# sensors.net
KiCad netlist of a schematic drawn in Altium Designer
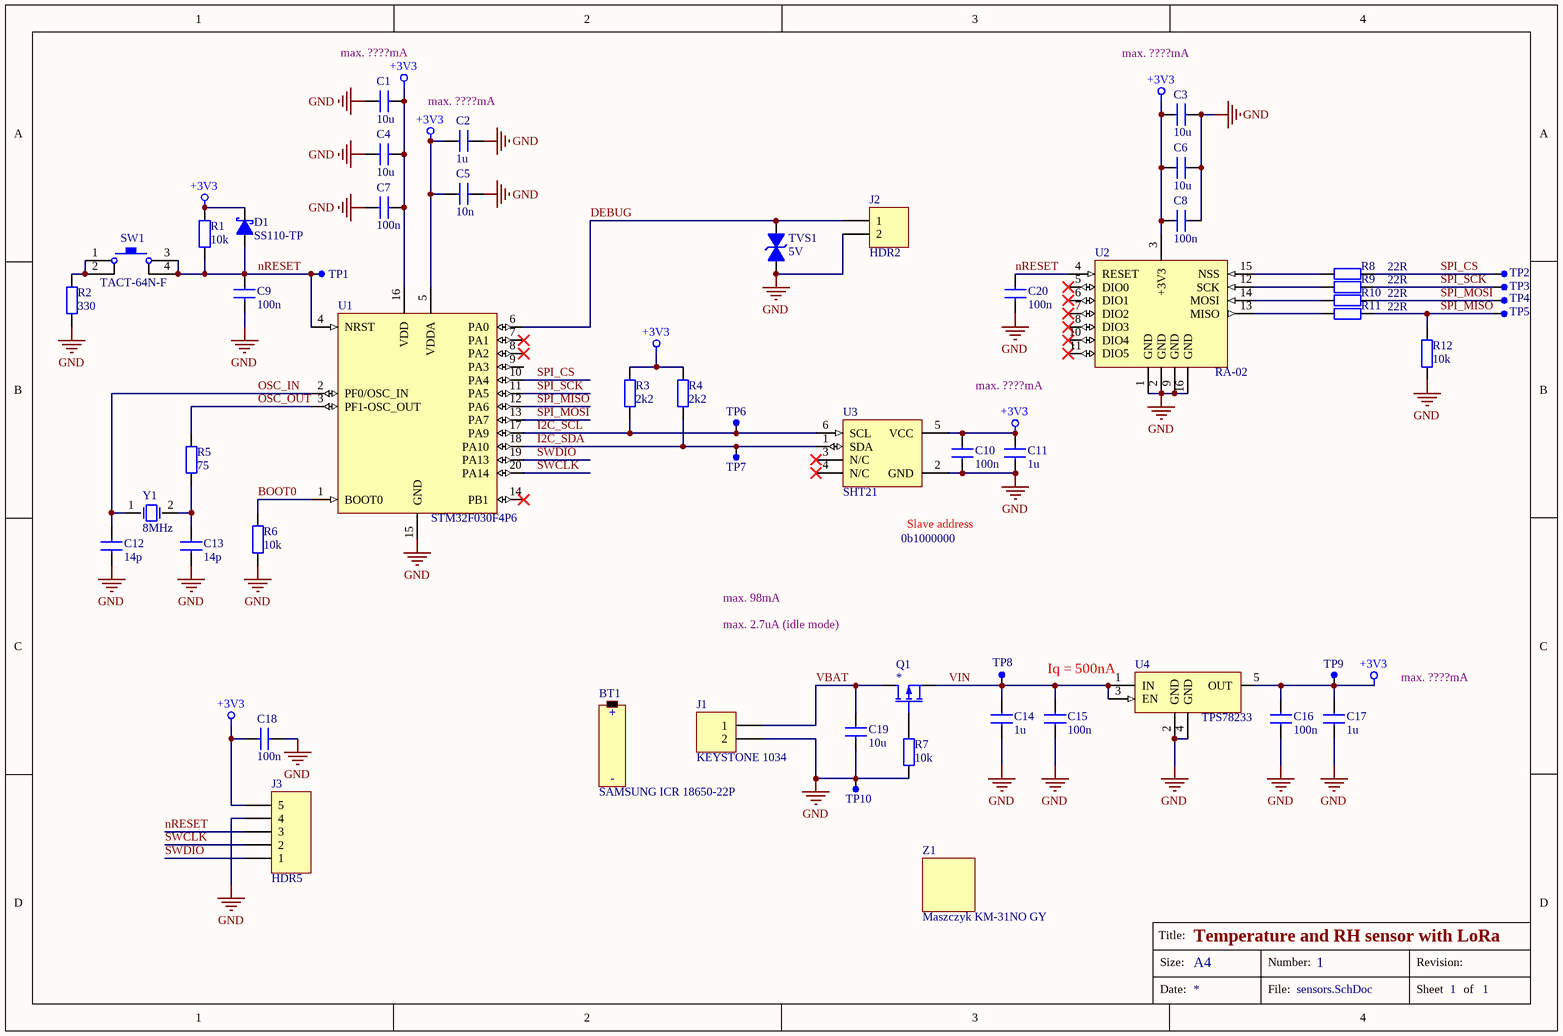
[diagram p0: sensors.SchDoc]

(export (version "E")
  (design (tool "Eeschema 10.0.6"))
  (components
    (comp (ref "BT1")
      (value "SAMSUNG ICR 18650-22P")
      (footprint "BATTERY_18650")
      (description "Multicell Battery")
      (fields (field (name "PUBLISHER") "Altium Limited"))
      (libsource (lib "mechanical") (part "Battery"))
    )
    (comp (ref "C1")
      (value "10u")
      (footprint "C_0805")
      (description "Capacitor")
      (libsource (lib "passive") (part "Capacitor"))
    )
    (comp (ref "C2")
      (value "1u")
      (footprint "C_0805")
      (description "Capacitor")
      (libsource (lib "passive") (part "Capacitor"))
    )
    (comp (ref "C3")
      (value "10u")
      (footprint "C_0805")
      (description "Capacitor")
      (libsource (lib "passive") (part "Capacitor"))
    )
    (comp (ref "C4")
      (value "10u")
      (footprint "C_0805")
      (description "Capacitor")
      (libsource (lib "passive") (part "Capacitor"))
    )
    (comp (ref "C5")
      (value "10n")
      (footprint "C_0805")
      (description "Capacitor")
      (libsource (lib "passive") (part "Capacitor"))
    )
    (comp (ref "C6")
      (value "10u")
      (footprint "C_0805")
      (description "Capacitor")
      (libsource (lib "passive") (part "Capacitor"))
    )
    (comp (ref "C7")
      (value "100n")
      (footprint "C_0805")
      (description "Capacitor")
      (libsource (lib "passive") (part "Capacitor"))
    )
    (comp (ref "C8")
      (value "100n")
      (footprint "C_0805")
      (description "Capacitor")
      (libsource (lib "passive") (part "Capacitor"))
    )
    (comp (ref "C9")
      (value "100n")
      (footprint "C_0805")
      (description "Capacitor")
      (libsource (lib "passive") (part "Capacitor"))
    )
    (comp (ref "C10")
      (value "100n")
      (footprint "C_0805")
      (description "Capacitor")
      (libsource (lib "boxer_pas") (part "Capacitor"))
    )
    (comp (ref "C11")
      (value "1u")
      (footprint "C_0805")
      (description "Capacitor")
      (libsource (lib "passive") (part "Capacitor"))
    )
    (comp (ref "C12")
      (value "14p")
      (footprint "C_0805")
      (description "Capacitor")
      (libsource (lib "passive") (part "Capacitor"))
    )
    (comp (ref "C13")
      (value "14p")
      (footprint "C_0805")
      (description "Capacitor")
      (libsource (lib "passive") (part "Capacitor"))
    )
    (comp (ref "C14")
      (value "1u")
      (footprint "C_0805")
      (description "Capacitor")
      (libsource (lib "passive") (part "Capacitor"))
    )
    (comp (ref "C15")
      (value "100n")
      (footprint "C_0805")
      (description "Capacitor")
      (libsource (lib "boxer_pas") (part "Capacitor"))
    )
    (comp (ref "C16")
      (value "100n")
      (footprint "C_0805")
      (description "Capacitor")
      (libsource (lib "boxer_pas") (part "Capacitor"))
    )
    (comp (ref "C17")
      (value "1u")
      (footprint "C_0805")
      (description "Capacitor")
      (libsource (lib "passive") (part "Capacitor"))
    )
    (comp (ref "C18")
      (value "100n")
      (footprint "C_0805")
      (description "Capacitor")
      (libsource (lib "passive") (part "Capacitor"))
    )
    (comp (ref "C19")
      (value "10u")
      (footprint "C_0805")
      (description "Capacitor")
      (libsource (lib "passive") (part "Capacitor"))
    )
    (comp (ref "C20")
      (value "100n")
      (footprint "C_0805")
      (description "Capacitor")
      (libsource (lib "boxer_pas") (part "Capacitor"))
    )
    (comp (ref "D1")
      (value "SS110-TP")
      (footprint "D_1206")
      (description "Schottky Diode")
      (libsource (lib "passive") (part "Diode Schottky"))
    )
    (comp (ref "J1")
      (value "KEYSTONE 1034")
      (footprint "KEYSTONE 1043")
      (description "Header, 2-Pin")
      (fields (field (name "Comment") "Header 2"))
      (libsource (lib "") (part "Header 2_1"))
    )
    (comp (ref "J2")
      (value "HDR2")
      (footprint "header 2.54mm 2pin")
      (description "Header, 2-Pin")
      (fields (field (name "Comment") "Header 2"))
      (libsource (lib "mechanical") (part "Header 2"))
    )
    (comp (ref "J3")
      (value "HDR5")
      (footprint "header 2.54mm 5pin")
      (description "Header, 5-Pin")
      (fields (field (name "Comment") "Header 5"))
      (libsource (lib "mechanical") (part "Header 5"))
    )
    (comp (ref "Q1")
      (value "MOSFET-P")
      (footprint "SOT-23")
      (description "P-Channel MOSFET")
      (fields (field (name "ALTIUM_VALUE") "*"))
      (libsource (lib "passive") (part "MOSFET-P"))
    )
    (comp (ref "R1")
      (value "10k")
      (footprint "R_0805")
      (description "Resistor")
      (libsource (lib "passive") (part "Resistor"))
    )
    (comp (ref "R2")
      (value "330")
      (footprint "R_0805")
      (description "Resistor")
      (libsource (lib "passive") (part "Resistor"))
    )
    (comp (ref "R3")
      (value "2k2")
      (footprint "R_0805")
      (description "Resistor")
      (libsource (lib "passive") (part "Resistor"))
    )
    (comp (ref "R4")
      (value "2k2")
      (footprint "R_0805")
      (description "Resistor")
      (libsource (lib "passive") (part "Resistor"))
    )
    (comp (ref "R5")
      (value "75")
      (footprint "R_0805")
      (description "Resistor")
      (libsource (lib "passive") (part "Resistor"))
    )
    (comp (ref "R6")
      (value "10k")
      (footprint "R_0805")
      (description "Resistor")
      (libsource (lib "passive") (part "Resistor"))
    )
    (comp (ref "R7")
      (value "10k")
      (footprint "R_0805")
      (description "Resistor")
      (libsource (lib "passive") (part "Resistor"))
    )
    (comp (ref "R8")
      (value "22R")
      (footprint "R_0805")
      (description "Resistor")
      (libsource (lib "") (part "Resistor_1"))
    )
    (comp (ref "R9")
      (value "22R")
      (footprint "R_0805")
      (description "Resistor")
      (libsource (lib "") (part "Resistor_1"))
    )
    (comp (ref "R10")
      (value "22R")
      (footprint "R_0805")
      (description "Resistor")
      (libsource (lib "") (part "Resistor_1"))
    )
    (comp (ref "R11")
      (value "22R")
      (footprint "R_0805")
      (description "Resistor")
      (libsource (lib "") (part "Resistor_1"))
    )
    (comp (ref "R12")
      (value "10k")
      (footprint "R_1206")
      (description "Resistor")
      (libsource (lib "passive") (part "Resistor"))
    )
    (comp (ref "SW1")
      (value "TACT-64N-F")
      (footprint "SPST_NO_1301")
      (description "Switch 4 Pins")
      (fields (field (name "Comment") "Switch-PB 4 Pins"))
      (libsource (lib "mechanical") (part "Switch-PB 4 Pins"))
    )
    (comp (ref "TP1")
      (value "TEST PAD")
      (footprint "PIN")
      (description "PAD 1.5mm")
      (libsource (lib "mechanical") (part "TEST_PAD"))
    )
    (comp (ref "TP2")
      (value "TEST PAD")
      (footprint "PIN")
      (description "PAD 1.5mm")
      (libsource (lib "mechanical") (part "TEST_PAD"))
    )
    (comp (ref "TP3")
      (value "TEST PAD")
      (footprint "PIN")
      (description "PAD 1.5mm")
      (libsource (lib "mechanical") (part "TEST_PAD"))
    )
    (comp (ref "TP4")
      (value "TEST PAD")
      (footprint "PIN")
      (description "PAD 1.5mm")
      (libsource (lib "mechanical") (part "TEST_PAD"))
    )
    (comp (ref "TP5")
      (value "TEST PAD")
      (footprint "PIN")
      (description "PAD 1.5mm")
      (libsource (lib "mechanical") (part "TEST_PAD"))
    )
    (comp (ref "TP6")
      (value "TEST PAD")
      (footprint "PIN")
      (description "PAD 1.5mm")
      (libsource (lib "mechanical") (part "TEST_PAD"))
    )
    (comp (ref "TP7")
      (value "TEST PAD")
      (footprint "PIN")
      (description "PAD 1.5mm")
      (libsource (lib "mechanical") (part "TEST_PAD"))
    )
    (comp (ref "TP8")
      (value "TEST PAD")
      (footprint "PIN")
      (description "PAD 1.5mm")
      (libsource (lib "mechanical") (part "TEST_PAD"))
    )
    (comp (ref "TP9")
      (value "TEST PAD")
      (footprint "PIN")
      (description "PAD 1.5mm")
      (libsource (lib "mechanical") (part "TEST_PAD"))
    )
    (comp (ref "TP10")
      (value "TEST PAD")
      (footprint "PIN")
      (description "PAD 1.5mm")
      (libsource (lib "mechanical") (part "TEST_PAD"))
    )
    (comp (ref "TVS1")
      (value "5V")
      (footprint "D_1206")
      (description "Transil")
      (fields (field (name "Comment") "SMAJ5.0ALFCT-ND"))
      (libsource (lib "passive") (part "Transil"))
    )
    (comp (ref "U1")
      (value "STM32F030F4P6")
      (footprint "TSSOP20")
      (description "Mikrokontroler ARM; Flash:16kB; 48MHz; SRAM:4kB; TSSOP20")
      (libsource (lib "digital") (part "STM32F030F4P6"))
    )
    (comp (ref "U2")
      (value "RA-02")
      (footprint "RA-02")
      (description "LoRa RA-02 SX1278 433MHz")
      (libsource (lib "digital") (part "RA-02 SX1278"))
    )
    (comp (ref "U3")
      (value "SHT21")
      (footprint "DFN6")
      (description "Humidity and Temperature Sensor IC")
      (libsource (lib "boxer_ic") (part "SHT21"))
    )
    (comp (ref "U4")
      (value "TPS78233")
      (footprint "SOP5(6)")
      (description "150-mA, ultra-low quiescent qurrent (500 nA) low-dropout linear regulator")
      (libsource (lib "digital") (part "TPS78233"))
    )
    (comp (ref "Y1")
      (value "8MHz")
      (footprint "CFPX_217")
      (description "Crystal Oscillator")
      (fields (field (name "Comment") "7A-8.000MAAE-T"))
      (libsource (lib "passive") (part "XTAL"))
    )
    (comp (ref "Z1")
      (value "Maszczyk KM-31NO GY")
      (footprint "KM-31NO GY")
      (description "X:80mm; Y:114mm; Z:32mm; wentylowana; ABS")
      (libsource (lib "mechanical") (part "KM-31NO GY"))
    )
  )
  (nets
    (net (code "1") (name "+3V3") (class "Default")
      (node (ref "C1") (pin "1") (pinfunction "1_1") (pintype "passive"))
      (node (ref "C10") (pin "2") (pinfunction "2_2") (pintype "passive"))
      (node (ref "C11") (pin "1") (pinfunction "1_1") (pintype "passive"))
      (node (ref "C16") (pin "2") (pinfunction "2_2") (pintype "passive"))
      (node (ref "C17") (pin "1") (pinfunction "1_1") (pintype "passive"))
      (node (ref "C18") (pin "2") (pinfunction "2_2") (pintype "passive"))
      (node (ref "C2") (pin "2") (pinfunction "2_2") (pintype "passive"))
      (node (ref "C3") (pin "2") (pinfunction "2_2") (pintype "passive"))
      (node (ref "C4") (pin "1") (pinfunction "1_1") (pintype "passive"))
      (node (ref "C5") (pin "2") (pinfunction "2_2") (pintype "passive"))
      (node (ref "C6") (pin "2") (pinfunction "2_2") (pintype "passive"))
      (node (ref "C7") (pin "1") (pinfunction "1_1") (pintype "passive"))
      (node (ref "C8") (pin "2") (pinfunction "2_2") (pintype "passive"))
      (node (ref "D1") (pin "2") (pinfunction "K_2") (pintype "passive"))
      (node (ref "J3") (pin "5") (pinfunction "5_5") (pintype "passive"))
      (node (ref "R1") (pin "2") (pinfunction "2_2") (pintype "passive"))
      (node (ref "R3") (pin "2") (pinfunction "2_2") (pintype "passive"))
      (node (ref "R4") (pin "2") (pinfunction "2_2") (pintype "passive"))
      (node (ref "TP9") (pin "1") (pinfunction "1_1") (pintype "passive"))
      (node (ref "U1") (pin "16") (pinfunction "VDD_16") (pintype "power_in"))
      (node (ref "U1") (pin "5") (pinfunction "VDDA_5") (pintype "power_in"))
      (node (ref "U2") (pin "3") (pinfunction "+3V3_3") (pintype "power_in"))
      (node (ref "U3") (pin "5") (pinfunction "VCC_5") (pintype "power_in"))
      (node (ref "U4") (pin "5") (pinfunction "OUT_5") (pintype "power_in"))
    )
    (net (code "2") (name "/BOOT0") (class "Default")
      (node (ref "R6") (pin "2") (pinfunction "2_2") (pintype "passive"))
      (node (ref "U1") (pin "1") (pinfunction "BOOT0_1") (pintype "input"))
    )
    (net (code "3") (name "/DEBUG") (class "Default")
      (node (ref "J2") (pin "1") (pinfunction "1_1") (pintype "passive"))
      (node (ref "TVS1") (pin "2") (pinfunction "K_2") (pintype "passive"))
      (node (ref "U1") (pin "6") (pinfunction "PA0_6") (pintype "bidirectional"))
    )
    (net (code "4") (name "/I2C_SCL") (class "Default")
      (node (ref "R3") (pin "1") (pinfunction "1_1") (pintype "passive"))
      (node (ref "TP6") (pin "1") (pinfunction "1_1") (pintype "passive"))
      (node (ref "U1") (pin "17") (pinfunction "PA9_17") (pintype "bidirectional"))
      (node (ref "U3") (pin "6") (pinfunction "SCL_6") (pintype "input"))
    )
    (net (code "5") (name "/I2C_SDA") (class "Default")
      (node (ref "R4") (pin "1") (pinfunction "1_1") (pintype "passive"))
      (node (ref "TP7") (pin "1") (pinfunction "1_1") (pintype "passive"))
      (node (ref "U1") (pin "18") (pinfunction "PA10_18") (pintype "bidirectional"))
      (node (ref "U3") (pin "1") (pinfunction "SDA_1") (pintype "bidirectional"))
    )
    (net (code "6") (name "/OSC_IN") (class "Default")
      (node (ref "C12") (pin "2") (pinfunction "2_2") (pintype "passive"))
      (node (ref "U1") (pin "2") (pinfunction "PF0/OSC_IN_2") (pintype "bidirectional"))
      (node (ref "Y1") (pin "1") (pinfunction "OSC1_1") (pintype "passive"))
    )
    (net (code "7") (name "/OSC_OUT") (class "Default")
      (node (ref "R5") (pin "2") (pinfunction "2_2") (pintype "passive"))
      (node (ref "U1") (pin "3") (pinfunction "PF1-OSC_OUT_3") (pintype "bidirectional"))
    )
    (net (code "8") (name "/SPI_CS") (class "Default")
      (node (ref "R8") (pin "1") (pinfunction "1_1") (pintype "passive"))
      (node (ref "TP2") (pin "1") (pinfunction "1_1") (pintype "passive"))
      (node (ref "U1") (pin "10") (pinfunction "PA4_10") (pintype "bidirectional"))
    )
    (net (code "9") (name "/SPI_MISO") (class "Default")
      (node (ref "R11") (pin "1") (pinfunction "1_1") (pintype "passive"))
      (node (ref "R12") (pin "2") (pinfunction "2_2") (pintype "passive"))
      (node (ref "TP5") (pin "1") (pinfunction "1_1") (pintype "passive"))
      (node (ref "U1") (pin "12") (pinfunction "PA6_12") (pintype "bidirectional"))
    )
    (net (code "10") (name "/SPI_MOSI") (class "Default")
      (node (ref "R10") (pin "1") (pinfunction "1_1") (pintype "passive"))
      (node (ref "TP4") (pin "1") (pinfunction "1_1") (pintype "passive"))
      (node (ref "U1") (pin "13") (pinfunction "PA7_13") (pintype "bidirectional"))
    )
    (net (code "11") (name "/SPI_SCK") (class "Default")
      (node (ref "R9") (pin "1") (pinfunction "1_1") (pintype "passive"))
      (node (ref "TP3") (pin "1") (pinfunction "1_1") (pintype "passive"))
      (node (ref "U1") (pin "11") (pinfunction "PA5_11") (pintype "bidirectional"))
    )
    (net (code "12") (name "/SWCLK") (class "Default")
      (node (ref "J3") (pin "2") (pinfunction "2_2") (pintype "passive"))
      (node (ref "U1") (pin "20") (pinfunction "PA14_20") (pintype "bidirectional"))
    )
    (net (code "13") (name "/SWDIO") (class "Default")
      (node (ref "J3") (pin "1") (pinfunction "1_1") (pintype "passive"))
      (node (ref "U1") (pin "19") (pinfunction "PA13_19") (pintype "bidirectional"))
    )
    (net (code "14") (name "/VBAT") (class "Default")
      (node (ref "C19") (pin "1") (pinfunction "1_1") (pintype "passive"))
      (node (ref "J1") (pin "1") (pinfunction "1_1") (pintype "passive"))
      (node (ref "Q1") (pin "3") (pinfunction "D_3") (pintype "passive"))
    )
    (net (code "15") (name "/VIN") (class "Default")
      (node (ref "C14") (pin "1") (pinfunction "1_1") (pintype "passive"))
      (node (ref "C15") (pin "2") (pinfunction "2_2") (pintype "passive"))
      (node (ref "Q1") (pin "2") (pinfunction "S_2") (pintype "passive"))
      (node (ref "TP8") (pin "1") (pinfunction "1_1") (pintype "passive"))
      (node (ref "U4") (pin "1") (pinfunction "IN_1") (pintype "power_in"))
      (node (ref "U4") (pin "3") (pinfunction "EN_3") (pintype "input"))
    )
    (net (code "16") (name "/nRESET") (class "Default")
      (node (ref "C20") (pin "2") (pinfunction "2_2") (pintype "passive"))
      (node (ref "C9") (pin "2") (pinfunction "2_2") (pintype "passive"))
      (node (ref "D1") (pin "1") (pinfunction "A_1") (pintype "passive"))
      (node (ref "J3") (pin "3") (pinfunction "3_3") (pintype "passive"))
      (node (ref "R1") (pin "1") (pinfunction "1_1") (pintype "passive"))
      (node (ref "SW1") (pin "3") (pinfunction "3_3") (pintype "passive"))
      (node (ref "SW1") (pin "4") (pinfunction "4_4") (pintype "passive"))
      (node (ref "TP1") (pin "1") (pinfunction "1_1") (pintype "passive"))
      (node (ref "U1") (pin "4") (pinfunction "NRST_4") (pintype "input"))
      (node (ref "U2") (pin "4") (pinfunction "RESET_4") (pintype "input"))
    )
    (net (code "17") (name "GND") (class "Default")
      (node (ref "C1") (pin "2") (pinfunction "2_2") (pintype "passive"))
      (node (ref "C10") (pin "1") (pinfunction "1_1") (pintype "passive"))
      (node (ref "C11") (pin "2") (pinfunction "2_2") (pintype "passive"))
      (node (ref "C12") (pin "1") (pinfunction "1_1") (pintype "passive"))
      (node (ref "C13") (pin "1") (pinfunction "1_1") (pintype "passive"))
      (node (ref "C14") (pin "2") (pinfunction "2_2") (pintype "passive"))
      (node (ref "C15") (pin "1") (pinfunction "1_1") (pintype "passive"))
      (node (ref "C16") (pin "1") (pinfunction "1_1") (pintype "passive"))
      (node (ref "C17") (pin "2") (pinfunction "2_2") (pintype "passive"))
      (node (ref "C18") (pin "1") (pinfunction "1_1") (pintype "passive"))
      (node (ref "C19") (pin "2") (pinfunction "2_2") (pintype "passive"))
      (node (ref "C2") (pin "1") (pinfunction "1_1") (pintype "passive"))
      (node (ref "C20") (pin "1") (pinfunction "1_1") (pintype "passive"))
      (node (ref "C3") (pin "1") (pinfunction "1_1") (pintype "passive"))
      (node (ref "C4") (pin "2") (pinfunction "2_2") (pintype "passive"))
      (node (ref "C5") (pin "1") (pinfunction "1_1") (pintype "passive"))
      (node (ref "C6") (pin "1") (pinfunction "1_1") (pintype "passive"))
      (node (ref "C7") (pin "2") (pinfunction "2_2") (pintype "passive"))
      (node (ref "C8") (pin "1") (pinfunction "1_1") (pintype "passive"))
      (node (ref "C9") (pin "1") (pinfunction "1_1") (pintype "passive"))
      (node (ref "J1") (pin "2") (pinfunction "2_2") (pintype "passive"))
      (node (ref "J2") (pin "2") (pinfunction "2_2") (pintype "passive"))
      (node (ref "J3") (pin "4") (pinfunction "4_4") (pintype "passive"))
      (node (ref "R12") (pin "1") (pinfunction "1_1") (pintype "passive"))
      (node (ref "R2") (pin "1") (pinfunction "1_1") (pintype "passive"))
      (node (ref "R6") (pin "1") (pinfunction "1_1") (pintype "passive"))
      (node (ref "R7") (pin "1") (pinfunction "1_1") (pintype "passive"))
      (node (ref "TP10") (pin "1") (pinfunction "1_1") (pintype "passive"))
      (node (ref "TVS1") (pin "1") (pinfunction "A_1") (pintype "passive"))
      (node (ref "U1") (pin "15") (pinfunction "GND_15") (pintype "power_in"))
      (node (ref "U2") (pin "1") (pinfunction "GND_1") (pintype "power_in"))
      (node (ref "U2") (pin "16") (pinfunction "GND_16") (pintype "power_in"))
      (node (ref "U2") (pin "2") (pinfunction "GND_2") (pintype "power_in"))
      (node (ref "U2") (pin "9") (pinfunction "GND_9") (pintype "power_in"))
      (node (ref "U3") (pin "2") (pinfunction "GND_2") (pintype "power_in"))
      (node (ref "U4") (pin "2") (pinfunction "GND_2") (pintype "power_in"))
      (node (ref "U4") (pin "4") (pinfunction "GND_4") (pintype "power_in"))
    )
    (net (code "18") (name "Net-(Q1-G)") (class "Default")
      (node (ref "Q1") (pin "1") (pinfunction "G_1") (pintype "passive"))
      (node (ref "R7") (pin "2") (pinfunction "2_2") (pintype "passive"))
    )
    (net (code "19") (name "Net-(R2-Pad2)") (class "Default")
      (node (ref "R2") (pin "2") (pinfunction "2_2") (pintype "passive"))
      (node (ref "SW1") (pin "1") (pinfunction "1_1") (pintype "passive"))
      (node (ref "SW1") (pin "2") (pinfunction "2_2") (pintype "passive"))
    )
    (net (code "20") (name "Net-(U2-MISO)") (class "Default")
      (node (ref "R11") (pin "2") (pinfunction "2_2") (pintype "passive"))
      (node (ref "U2") (pin "13") (pinfunction "MISO_13") (pintype "output"))
    )
    (net (code "21") (name "Net-(U2-MOSI)") (class "Default")
      (node (ref "R10") (pin "2") (pinfunction "2_2") (pintype "passive"))
      (node (ref "U2") (pin "14") (pinfunction "MOSI_14") (pintype "input"))
    )
    (net (code "22") (name "Net-(U2-NSS)") (class "Default")
      (node (ref "R8") (pin "2") (pinfunction "2_2") (pintype "passive"))
      (node (ref "U2") (pin "15") (pinfunction "NSS_15") (pintype "input"))
    )
    (net (code "23") (name "Net-(U2-SCK)") (class "Default")
      (node (ref "R9") (pin "2") (pinfunction "2_2") (pintype "passive"))
      (node (ref "U2") (pin "12") (pinfunction "SCK_12") (pintype "input"))
    )
    (net (code "24") (name "Net-(Y1-OSC2)") (class "Default")
      (node (ref "C13") (pin "2") (pinfunction "2_2") (pintype "passive"))
      (node (ref "R5") (pin "1") (pinfunction "1_1") (pintype "passive"))
      (node (ref "Y1") (pin "2") (pinfunction "OSC2_2") (pintype "passive"))
    )
    (net (code "25") (name "unconnected-(U1-PA1-Pad7)") (class "Default")
      (node (ref "U1") (pin "7") (pinfunction "PA1_7") (pintype "bidirectional+no_connect"))
    )
    (net (code "26") (name "unconnected-(U1-PA2-Pad8)") (class "Default")
      (node (ref "U1") (pin "8") (pinfunction "PA2_8") (pintype "bidirectional+no_connect"))
    )
    (net (code "27") (name "unconnected-(U1-PA3-Pad9)") (class "Default")
      (node (ref "U1") (pin "9") (pinfunction "PA3_9") (pintype "bidirectional"))
    )
    (net (code "28") (name "unconnected-(U1-PB1-Pad14)") (class "Default")
      (node (ref "U1") (pin "14") (pinfunction "PB1_14") (pintype "bidirectional+no_connect"))
    )
    (net (code "29") (name "unconnected-(U2-DIO0-Pad5)") (class "Default")
      (node (ref "U2") (pin "5") (pinfunction "DIO0_5") (pintype "bidirectional+no_connect"))
    )
    (net (code "30") (name "unconnected-(U2-DIO1-Pad6)") (class "Default")
      (node (ref "U2") (pin "6") (pinfunction "DIO1_6") (pintype "bidirectional+no_connect"))
    )
    (net (code "31") (name "unconnected-(U2-DIO2-Pad7)") (class "Default")
      (node (ref "U2") (pin "7") (pinfunction "DIO2_7") (pintype "bidirectional+no_connect"))
    )
    (net (code "32") (name "unconnected-(U2-DIO3-Pad8)") (class "Default")
      (node (ref "U2") (pin "8") (pinfunction "DIO3_8") (pintype "bidirectional+no_connect"))
    )
    (net (code "33") (name "unconnected-(U2-DIO4-Pad10)") (class "Default")
      (node (ref "U2") (pin "10") (pinfunction "DIO4_10") (pintype "bidirectional+no_connect"))
    )
    (net (code "34") (name "unconnected-(U2-DIO5-Pad11)") (class "Default")
      (node (ref "U2") (pin "11") (pinfunction "DIO5_11") (pintype "bidirectional+no_connect"))
    )
    (net (code "35") (name "unconnected-(U3-N{slash}C-Pad3)") (class "Default")
      (node (ref "U3") (pin "3") (pinfunction "N/C_3") (pintype "passive+no_connect"))
    )
    (net (code "36") (name "unconnected-(U3-N{slash}C-Pad4)") (class "Default")
      (node (ref "U3") (pin "4") (pinfunction "N/C_4") (pintype "passive+no_connect"))
    )
  )
)
